# PanoBoardV4.net
KiCad netlist of a schematic drawn in EAGLE
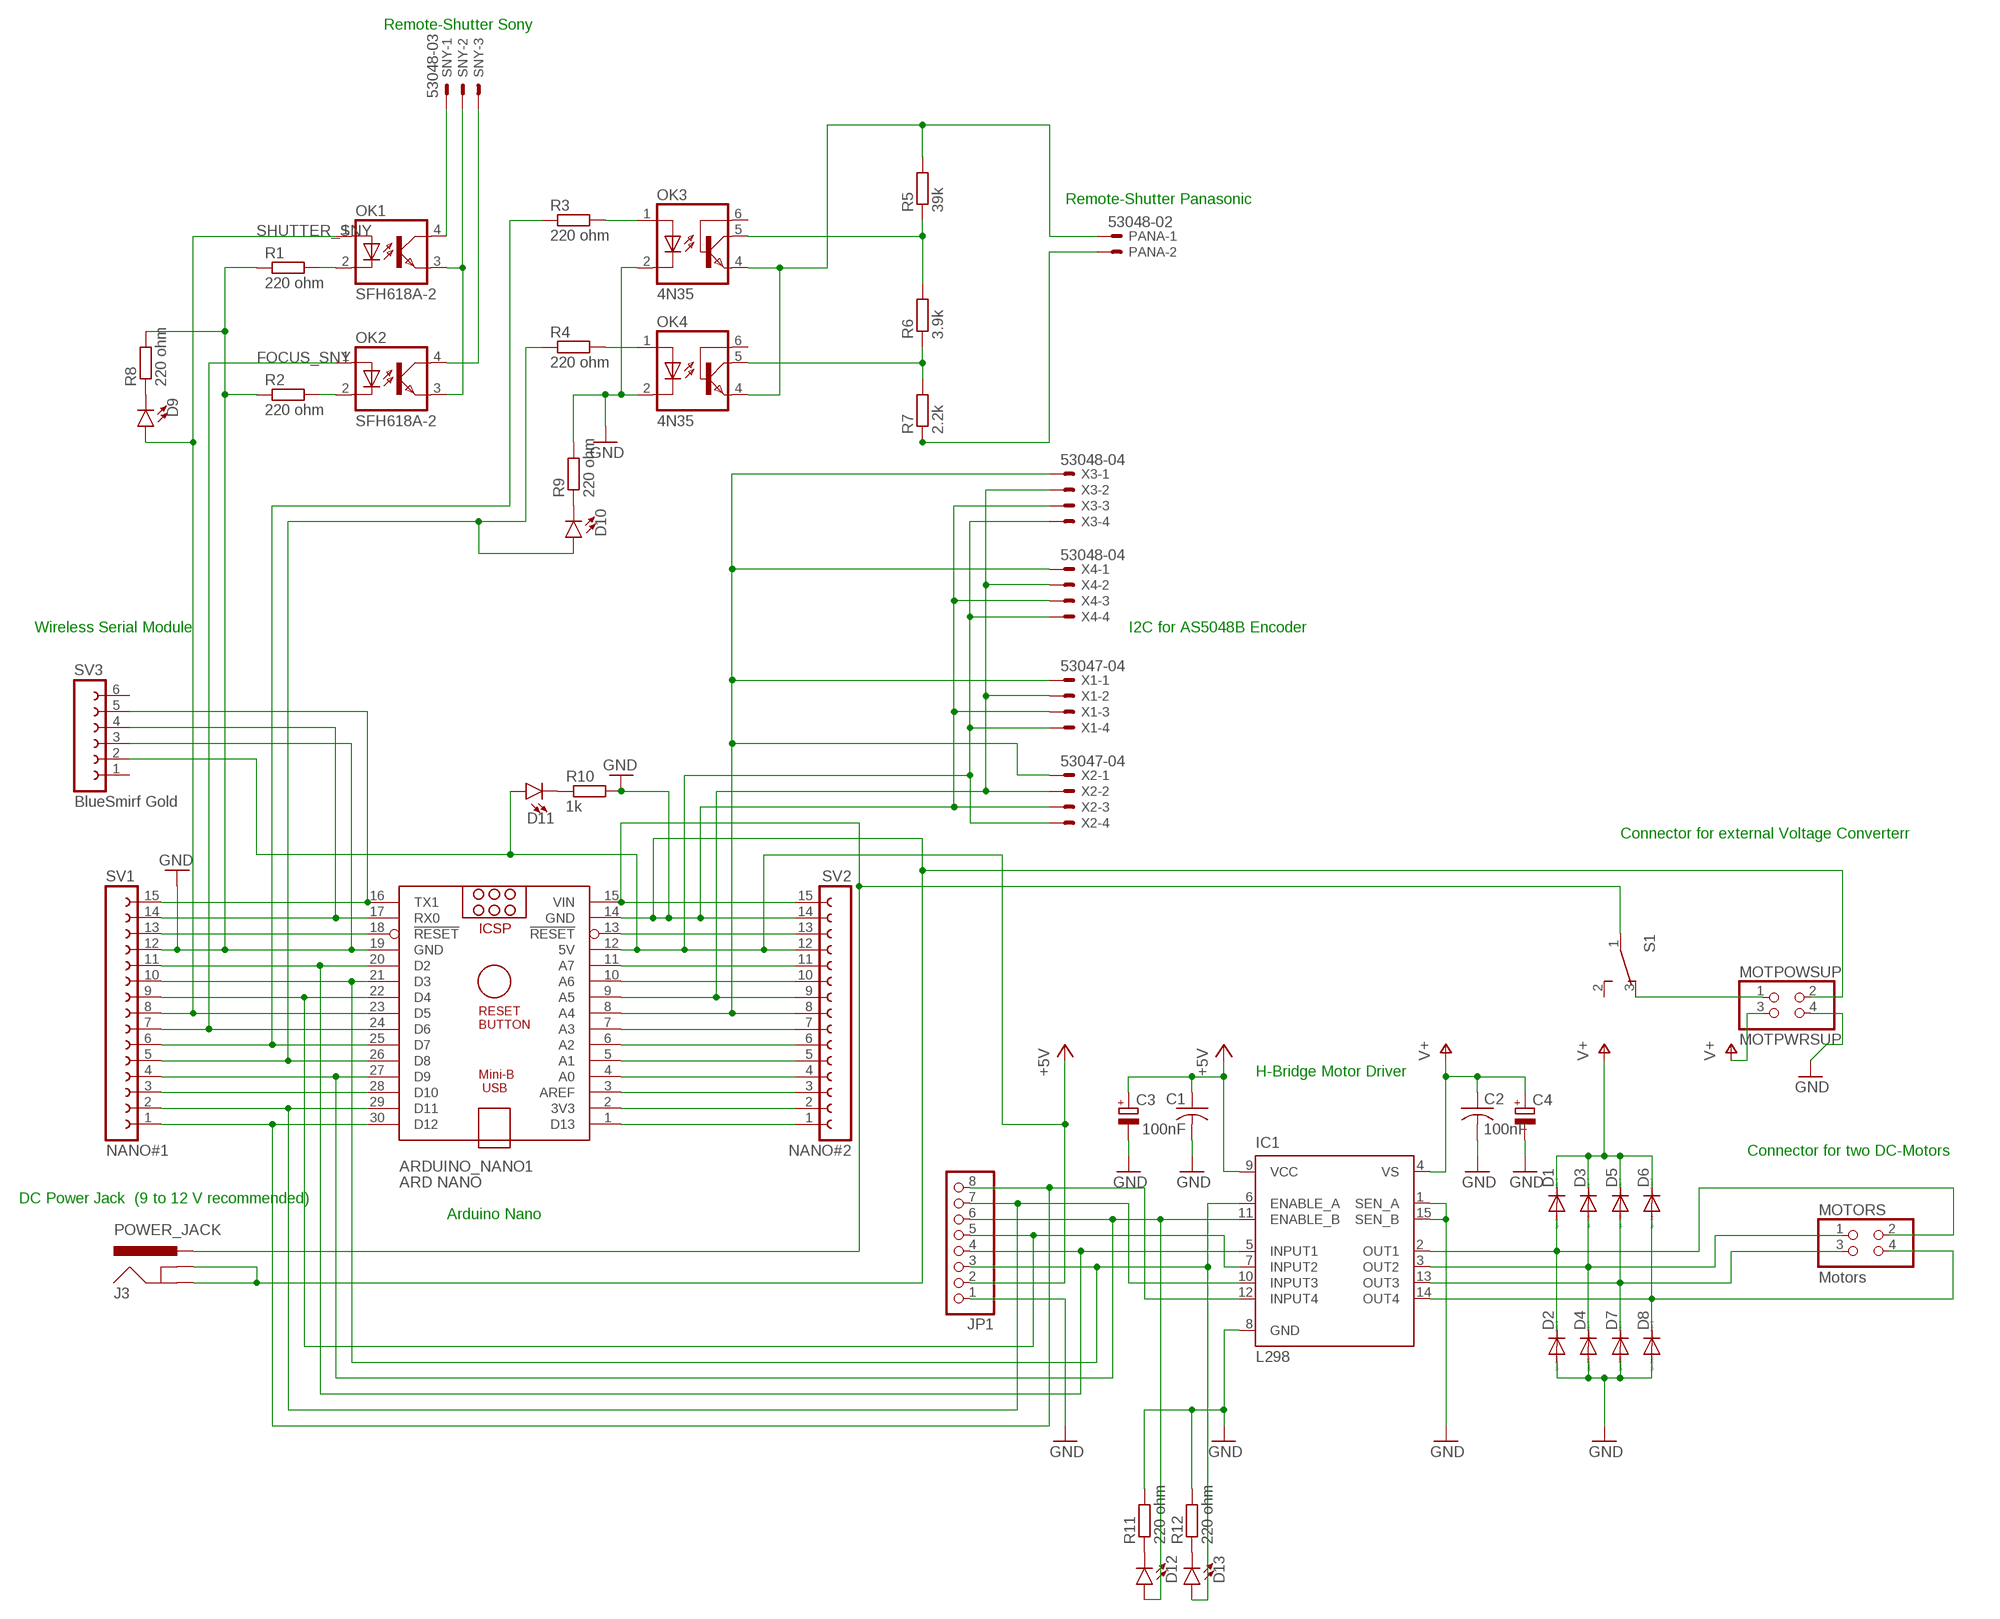
[diagram p0: schematic, sheet 1]

(export (version "E")
  (design (tool "Eeschema 10.0.6"))
  (components
    (comp (ref "ARDUINO_NANO1")
      (value "ARD NANO")
      (footprint "eagle-import:ARDUINO_NANO")
      (libsource (lib "eagle-import") (part "ARDUINO_NANO"))
    )
    (comp (ref "C1")
      (value "100nF")
      (footprint "eagle-import:C050-024X044")
      (libsource (lib "eagle-import") (part "C-US050-024X044"))
    )
    (comp (ref "C2")
      (value "100nF")
      (footprint "eagle-import:C050-024X044")
      (libsource (lib "eagle-import") (part "C-US050-024X044"))
    )
    (comp (ref "C3")
      (value "CPOL-EUE3.5-10")
      (footprint "eagle-import:E3,5-10")
      (libsource (lib "eagle-import") (part "CPOL-EUE3.5-10"))
    )
    (comp (ref "C4")
      (value "CPOL-EUE3.5-10")
      (footprint "eagle-import:E3,5-10")
      (libsource (lib "eagle-import") (part "CPOL-EUE3.5-10"))
    )
    (comp (ref "D1")
      (value "DIODE-D-5")
      (footprint "eagle-import:D-5")
      (libsource (lib "eagle-import") (part "DIODE-D-5"))
    )
    (comp (ref "D2")
      (value "DIODE-D-5")
      (footprint "eagle-import:D-5")
      (libsource (lib "eagle-import") (part "DIODE-D-5"))
    )
    (comp (ref "D3")
      (value "DIODE-D-5")
      (footprint "eagle-import:D-5")
      (libsource (lib "eagle-import") (part "DIODE-D-5"))
    )
    (comp (ref "D4")
      (value "DIODE-D-5")
      (footprint "eagle-import:D-5")
      (libsource (lib "eagle-import") (part "DIODE-D-5"))
    )
    (comp (ref "D5")
      (value "DIODE-D-5")
      (footprint "eagle-import:D-5")
      (libsource (lib "eagle-import") (part "DIODE-D-5"))
    )
    (comp (ref "D6")
      (value "DIODE-D-5")
      (footprint "eagle-import:D-5")
      (libsource (lib "eagle-import") (part "DIODE-D-5"))
    )
    (comp (ref "D7")
      (value "DIODE-D-5")
      (footprint "eagle-import:D-5")
      (libsource (lib "eagle-import") (part "DIODE-D-5"))
    )
    (comp (ref "D8")
      (value "DIODE-D-5")
      (footprint "eagle-import:D-5")
      (libsource (lib "eagle-import") (part "DIODE-D-5"))
    )
    (comp (ref "D9")
      (value "LED1206")
      (footprint "eagle-import:LED-1206")
      (libsource (lib "eagle-import") (part "LED1206"))
    )
    (comp (ref "D10")
      (value "LED1206")
      (footprint "eagle-import:LED-1206")
      (libsource (lib "eagle-import") (part "LED1206"))
    )
    (comp (ref "D11")
      (value "LED1206")
      (footprint "eagle-import:LED-1206")
      (libsource (lib "eagle-import") (part "LED1206"))
    )
    (comp (ref "D12")
      (value "LED1206")
      (footprint "eagle-import:LED-1206")
      (libsource (lib "eagle-import") (part "LED1206"))
    )
    (comp (ref "D13")
      (value "LED1206")
      (footprint "eagle-import:LED-1206")
      (libsource (lib "eagle-import") (part "LED1206"))
    )
    (comp (ref "IC1")
      (value "L298")
      (footprint "eagle-import:MULTIWATT-15")
      (libsource (lib "eagle-import") (part "L298"))
    )
    (comp (ref "J3")
      (value "POWER_JACK")
      (footprint "eagle-import:POWER_JACK_PTH")
      (libsource (lib "eagle-import") (part "POWER_JACK"))
    )
    (comp (ref "JP1")
      (value "PINHD-1X8")
      (footprint "eagle-import:1X08")
      (libsource (lib "eagle-import") (part "PINHD-1X8"))
    )
    (comp (ref "MOTORS")
      (value "Motors")
      (footprint "eagle-import:2X02")
      (libsource (lib "eagle-import") (part "PINHD-2X2"))
    )
    (comp (ref "MOTPOWSUP")
      (value "MOTPWRSUP")
      (footprint "eagle-import:2X02")
      (libsource (lib "eagle-import") (part "PINHD-2X2"))
    )
    (comp (ref "OK1")
      (value "SFH618A-2")
      (footprint "eagle-import:DIP4")
      (fields (field (name "MF") "VISHAY/TELEFUNKEN"))
      (libsource (lib "eagle-import") (part "SFH618?A-2"))
    )
    (comp (ref "OK2")
      (value "SFH618A-2")
      (footprint "eagle-import:DIP4")
      (fields (field (name "MF") "VISHAY/TELEFUNKEN"))
      (libsource (lib "eagle-import") (part "SFH618?A-2"))
    )
    (comp (ref "OK3")
      (value "4N35")
      (footprint "eagle-import:DIL06")
      (fields (field (name "MF") "FAIRCHILD SEMICONDUCTOR"))
      (libsource (lib "eagle-import") (part "4N35"))
    )
    (comp (ref "OK4")
      (value "4N35")
      (footprint "eagle-import:DIL06")
      (fields (field (name "MF") "FAIRCHILD SEMICONDUCTOR"))
      (libsource (lib "eagle-import") (part "4N35"))
    )
    (comp (ref "PANA")
      (value "53048-02")
      (footprint "eagle-import:53048-02")
      (fields (field (name "MF") "MOLEX") (field (name "MPN") "53048-0210"))
      (libsource (lib "eagle-import") (part "53?-02048"))
    )
    (comp (ref "R1")
      (value "220 ohm")
      (footprint "eagle-import:R1210")
      (libsource (lib "eagle-import") (part "R-EU_R1210"))
    )
    (comp (ref "R2")
      (value "220 ohm")
      (footprint "eagle-import:R1210")
      (libsource (lib "eagle-import") (part "R-EU_R1210"))
    )
    (comp (ref "R3")
      (value "220 ohm")
      (footprint "eagle-import:R1210")
      (libsource (lib "eagle-import") (part "R-EU_R1210"))
    )
    (comp (ref "R4")
      (value "220 ohm")
      (footprint "eagle-import:R1210")
      (libsource (lib "eagle-import") (part "R-EU_R1210"))
    )
    (comp (ref "R5")
      (value "39k")
      (footprint "eagle-import:R1210")
      (libsource (lib "eagle-import") (part "R-EU_R1210"))
    )
    (comp (ref "R6")
      (value "3.9k")
      (footprint "eagle-import:R1210")
      (libsource (lib "eagle-import") (part "R-EU_R1210"))
    )
    (comp (ref "R7")
      (value "2.2k")
      (footprint "eagle-import:R1210")
      (libsource (lib "eagle-import") (part "R-EU_R1210"))
    )
    (comp (ref "R8")
      (value "220 ohm")
      (footprint "eagle-import:R1210")
      (libsource (lib "eagle-import") (part "R-EU_R1210"))
    )
    (comp (ref "R9")
      (value "220 ohm")
      (footprint "eagle-import:R1210")
      (libsource (lib "eagle-import") (part "R-EU_R1210"))
    )
    (comp (ref "R10")
      (value "1k")
      (footprint "eagle-import:R1210")
      (libsource (lib "eagle-import") (part "R-EU_R1210"))
    )
    (comp (ref "R11")
      (value "220 ohm")
      (footprint "eagle-import:R1210")
      (libsource (lib "eagle-import") (part "R-EU_R1210"))
    )
    (comp (ref "R12")
      (value "220 ohm")
      (footprint "eagle-import:R1210")
      (libsource (lib "eagle-import") (part "R-EU_R1210"))
    )
    (comp (ref "S1")
      (value "450302014072")
      (footprint "eagle-import:450302014072")
      (libsource (lib "eagle-import") (part "450302014072"))
    )
    (comp (ref "SNY")
      (value "53048-03")
      (footprint "eagle-import:53048-03")
      (fields (field (name "MF") "WALDOM/MOLEX") (field (name "MPN") "53048-0310"))
      (libsource (lib "eagle-import") (part "53?-03048"))
    )
    (comp (ref "SV1")
      (value "NANO#1")
      (footprint "eagle-import:FE15")
      (libsource (lib "eagle-import") (part "FE15-1"))
    )
    (comp (ref "SV2")
      (value "NANO#2")
      (footprint "eagle-import:FE15")
      (libsource (lib "eagle-import") (part "FE15-1"))
    )
    (comp (ref "SV3")
      (value "BlueSmirf Gold")
      (footprint "eagle-import:FE06W")
      (libsource (lib "eagle-import") (part "FE06W"))
    )
    (comp (ref "X1")
      (value "53047-04")
      (footprint "eagle-import:53047-04")
      (fields (field (name "MF") "WALDOM/MOLEX") (field (name "MPN") "53047-0410"))
      (libsource (lib "eagle-import") (part "53?-04047"))
    )
    (comp (ref "X2")
      (value "53047-04")
      (footprint "eagle-import:53047-04")
      (fields (field (name "MF") "WALDOM/MOLEX") (field (name "MPN") "53047-0410"))
      (libsource (lib "eagle-import") (part "53?-04047"))
    )
    (comp (ref "X3")
      (value "53048-04")
      (footprint "eagle-import:53048-04")
      (fields (field (name "MF") "MOLEX") (field (name "MPN") "53048-0410"))
      (libsource (lib "eagle-import") (part "53?-04048"))
    )
    (comp (ref "X4")
      (value "53048-04")
      (footprint "eagle-import:53048-04")
      (fields (field (name "MF") "MOLEX") (field (name "MPN") "53048-0410"))
      (libsource (lib "eagle-import") (part "53?-04048"))
    )
  )
  (nets
    (net (code "1") (name "+5V") (class "Default")
      (node (ref "ARDUINO_NANO1") (pin "12") (pinfunction "5V_12") (pintype "power_in"))
      (node (ref "C1") (pin "1") (pinfunction "1_1") (pintype "passive"))
      (node (ref "C3") (pin "+") (pinfunction "+_+") (pintype "passive"))
      (node (ref "D11") (pin "A") (pinfunction "A_A") (pintype "passive"))
      (node (ref "IC1") (pin "9") (pinfunction "VCC_9") (pintype "power_in"))
      (node (ref "JP1") (pin "2") (pinfunction "2_2") (pintype "passive"))
      (node (ref "SV2") (pin "12") (pinfunction "12_12") (pintype "passive"))
      (node (ref "SV3") (pin "2") (pinfunction "2_2") (pintype "passive"))
      (node (ref "X1") (pin "4") (pinfunction "S_4") (pintype "passive"))
      (node (ref "X2") (pin "4") (pinfunction "S_4") (pintype "passive"))
      (node (ref "X3") (pin "4") (pinfunction "S_4") (pintype "passive"))
      (node (ref "X4") (pin "4") (pinfunction "S_4") (pintype "passive"))
    )
    (net (code "2") (name "/FOCUS_SNY") (class "Default")
      (node (ref "ARDUINO_NANO1") (pin "24") (pinfunction "D6_24") (pintype "bidirectional"))
      (node (ref "OK2") (pin "1") (pinfunction "A_1") (pintype "passive"))
      (node (ref "SV1") (pin "7") (pinfunction "7_7") (pintype "passive"))
    )
    (net (code "3") (name "/SHUTTER_SNY") (class "Default")
      (node (ref "ARDUINO_NANO1") (pin "23") (pinfunction "D5_23") (pintype "bidirectional"))
      (node (ref "D9") (pin "A") (pinfunction "A_A") (pintype "passive"))
      (node (ref "OK1") (pin "1") (pinfunction "A_1") (pintype "passive"))
      (node (ref "SV1") (pin "8") (pinfunction "8_8") (pintype "passive"))
    )
    (net (code "4") (name "GND") (class "Default")
      (node (ref "ARDUINO_NANO1") (pin "14") (pinfunction "GND_14") (pintype "power_in"))
      (node (ref "ARDUINO_NANO1") (pin "19") (pinfunction "GND_19") (pintype "power_in"))
      (node (ref "C1") (pin "2") (pinfunction "2_2") (pintype "passive"))
      (node (ref "C2") (pin "2") (pinfunction "2_2") (pintype "passive"))
      (node (ref "C3") (pin "-") (pinfunction "-_-") (pintype "passive"))
      (node (ref "C4") (pin "-") (pinfunction "-_-") (pintype "passive"))
      (node (ref "D2") (pin "A") (pinfunction "A_A") (pintype "passive"))
      (node (ref "D4") (pin "A") (pinfunction "A_A") (pintype "passive"))
      (node (ref "D7") (pin "A") (pinfunction "A_A") (pintype "passive"))
      (node (ref "D8") (pin "A") (pinfunction "A_A") (pintype "passive"))
      (node (ref "IC1") (pin "1") (pinfunction "SEN_A_1") (pintype "input"))
      (node (ref "IC1") (pin "15") (pinfunction "SEN_B_15") (pintype "input"))
      (node (ref "IC1") (pin "8") (pinfunction "GND_8") (pintype "power_in"))
      (node (ref "J3") (pin "GND") (pinfunction "GND_GND") (pintype "bidirectional"))
      (node (ref "J3") (pin "GNDBREAK") (pinfunction "GNDBREAK_GNDBREAK") (pintype "bidirectional"))
      (node (ref "JP1") (pin "1") (pinfunction "1_1") (pintype "passive"))
      (node (ref "MOTPOWSUP") (pin "2") (pinfunction "2_2") (pintype "passive"))
      (node (ref "MOTPOWSUP") (pin "4") (pinfunction "4_4") (pintype "passive"))
      (node (ref "OK3") (pin "2") (pinfunction "C_2") (pintype "passive"))
      (node (ref "OK4") (pin "2") (pinfunction "C_2") (pintype "passive"))
      (node (ref "R1") (pin "1") (pinfunction "1_1") (pintype "passive"))
      (node (ref "R10") (pin "2") (pinfunction "2_2") (pintype "passive"))
      (node (ref "R11") (pin "2") (pinfunction "2_2") (pintype "passive"))
      (node (ref "R12") (pin "2") (pinfunction "2_2") (pintype "passive"))
      (node (ref "R2") (pin "1") (pinfunction "1_1") (pintype "passive"))
      (node (ref "R8") (pin "2") (pinfunction "2_2") (pintype "passive"))
      (node (ref "R9") (pin "2") (pinfunction "2_2") (pintype "passive"))
      (node (ref "SV1") (pin "12") (pinfunction "12_12") (pintype "passive"))
      (node (ref "SV2") (pin "14") (pinfunction "14_14") (pintype "passive"))
      (node (ref "SV3") (pin "3") (pinfunction "3_3") (pintype "passive"))
      (node (ref "X1") (pin "3") (pinfunction "S_3") (pintype "passive"))
      (node (ref "X2") (pin "3") (pinfunction "S_3") (pintype "passive"))
      (node (ref "X3") (pin "3") (pinfunction "S_3") (pintype "passive"))
      (node (ref "X4") (pin "3") (pinfunction "S_3") (pintype "passive"))
    )
    (net (code "5") (name "Net-(ARDUINO_NANO1-3V3)") (class "Default")
      (node (ref "ARDUINO_NANO1") (pin "2") (pinfunction "3V3_2") (pintype "output"))
      (node (ref "SV2") (pin "2") (pinfunction "2_2") (pintype "passive"))
    )
    (net (code "6") (name "Net-(ARDUINO_NANO1-A0)") (class "Default")
      (node (ref "ARDUINO_NANO1") (pin "4") (pinfunction "A0_4") (pintype "bidirectional"))
      (node (ref "SV2") (pin "4") (pinfunction "4_4") (pintype "passive"))
    )
    (net (code "7") (name "Net-(ARDUINO_NANO1-A1)") (class "Default")
      (node (ref "ARDUINO_NANO1") (pin "5") (pinfunction "A1_5") (pintype "bidirectional"))
      (node (ref "SV2") (pin "5") (pinfunction "5_5") (pintype "passive"))
    )
    (net (code "8") (name "Net-(ARDUINO_NANO1-A2)") (class "Default")
      (node (ref "ARDUINO_NANO1") (pin "6") (pinfunction "A2_6") (pintype "bidirectional"))
      (node (ref "SV2") (pin "6") (pinfunction "6_6") (pintype "passive"))
    )
    (net (code "9") (name "Net-(ARDUINO_NANO1-A3)") (class "Default")
      (node (ref "ARDUINO_NANO1") (pin "7") (pinfunction "A3_7") (pintype "bidirectional"))
      (node (ref "SV2") (pin "7") (pinfunction "7_7") (pintype "passive"))
    )
    (net (code "10") (name "Net-(ARDUINO_NANO1-A4)") (class "Default")
      (node (ref "ARDUINO_NANO1") (pin "8") (pinfunction "A4_8") (pintype "bidirectional"))
      (node (ref "SV2") (pin "8") (pinfunction "8_8") (pintype "passive"))
      (node (ref "X1") (pin "1") (pinfunction "S_1") (pintype "passive"))
      (node (ref "X2") (pin "1") (pinfunction "S_1") (pintype "passive"))
      (node (ref "X3") (pin "1") (pinfunction "S_1") (pintype "passive"))
      (node (ref "X4") (pin "1") (pinfunction "S_1") (pintype "passive"))
    )
    (net (code "11") (name "Net-(ARDUINO_NANO1-A5)") (class "Default")
      (node (ref "ARDUINO_NANO1") (pin "9") (pinfunction "A5_9") (pintype "bidirectional"))
      (node (ref "SV2") (pin "9") (pinfunction "9_9") (pintype "passive"))
      (node (ref "X1") (pin "2") (pinfunction "S_2") (pintype "passive"))
      (node (ref "X2") (pin "2") (pinfunction "S_2") (pintype "passive"))
      (node (ref "X3") (pin "2") (pinfunction "S_2") (pintype "passive"))
      (node (ref "X4") (pin "2") (pinfunction "S_2") (pintype "passive"))
    )
    (net (code "12") (name "Net-(ARDUINO_NANO1-A6)") (class "Default")
      (node (ref "ARDUINO_NANO1") (pin "10") (pinfunction "A6_10") (pintype "bidirectional"))
      (node (ref "SV2") (pin "10") (pinfunction "10_10") (pintype "passive"))
    )
    (net (code "13") (name "Net-(ARDUINO_NANO1-A7)") (class "Default")
      (node (ref "ARDUINO_NANO1") (pin "11") (pinfunction "A7_11") (pintype "bidirectional"))
      (node (ref "SV2") (pin "11") (pinfunction "11_11") (pintype "passive"))
    )
    (net (code "14") (name "Net-(ARDUINO_NANO1-AREF)") (class "Default")
      (node (ref "ARDUINO_NANO1") (pin "3") (pinfunction "AREF_3") (pintype "input"))
      (node (ref "SV2") (pin "3") (pinfunction "3_3") (pintype "passive"))
    )
    (net (code "15") (name "Net-(ARDUINO_NANO1-D2)") (class "Default")
      (node (ref "ARDUINO_NANO1") (pin "20") (pinfunction "D2_20") (pintype "bidirectional"))
      (node (ref "IC1") (pin "5") (pinfunction "INPUT1_5") (pintype "input"))
      (node (ref "JP1") (pin "4") (pinfunction "4_4") (pintype "passive"))
      (node (ref "SV1") (pin "11") (pinfunction "11_11") (pintype "passive"))
    )
    (net (code "16") (name "Net-(ARDUINO_NANO1-D3)") (class "Default")
      (node (ref "ARDUINO_NANO1") (pin "21") (pinfunction "D3_21") (pintype "bidirectional"))
      (node (ref "D13") (pin "A") (pinfunction "A_A") (pintype "passive"))
      (node (ref "IC1") (pin "6") (pinfunction "ENABLE_A_6") (pintype "input"))
      (node (ref "JP1") (pin "3") (pinfunction "3_3") (pintype "passive"))
      (node (ref "SV1") (pin "10") (pinfunction "10_10") (pintype "passive"))
    )
    (net (code "17") (name "Net-(ARDUINO_NANO1-D4)") (class "Default")
      (node (ref "ARDUINO_NANO1") (pin "22") (pinfunction "D4_22") (pintype "bidirectional"))
      (node (ref "IC1") (pin "7") (pinfunction "INPUT2_7") (pintype "input"))
      (node (ref "JP1") (pin "5") (pinfunction "5_5") (pintype "passive"))
      (node (ref "SV1") (pin "9") (pinfunction "9_9") (pintype "passive"))
    )
    (net (code "18") (name "Net-(ARDUINO_NANO1-D7)") (class "Default")
      (node (ref "ARDUINO_NANO1") (pin "25") (pinfunction "D7_25") (pintype "bidirectional"))
      (node (ref "R3") (pin "1") (pinfunction "1_1") (pintype "passive"))
      (node (ref "SV1") (pin "6") (pinfunction "6_6") (pintype "passive"))
    )
    (net (code "19") (name "Net-(ARDUINO_NANO1-D8)") (class "Default")
      (node (ref "ARDUINO_NANO1") (pin "26") (pinfunction "D8_26") (pintype "bidirectional"))
      (node (ref "D10") (pin "A") (pinfunction "A_A") (pintype "passive"))
      (node (ref "R4") (pin "1") (pinfunction "1_1") (pintype "passive"))
      (node (ref "SV1") (pin "5") (pinfunction "5_5") (pintype "passive"))
    )
    (net (code "20") (name "Net-(ARDUINO_NANO1-D9)") (class "Default")
      (node (ref "ARDUINO_NANO1") (pin "27") (pinfunction "D9_27") (pintype "bidirectional"))
      (node (ref "D12") (pin "A") (pinfunction "A_A") (pintype "passive"))
      (node (ref "IC1") (pin "11") (pinfunction "ENABLE_B_11") (pintype "input"))
      (node (ref "JP1") (pin "6") (pinfunction "6_6") (pintype "passive"))
      (node (ref "SV1") (pin "4") (pinfunction "4_4") (pintype "passive"))
    )
    (net (code "21") (name "Net-(ARDUINO_NANO1-D10)") (class "Default")
      (node (ref "ARDUINO_NANO1") (pin "28") (pinfunction "D10_28") (pintype "bidirectional"))
      (node (ref "SV1") (pin "3") (pinfunction "3_3") (pintype "passive"))
    )
    (net (code "22") (name "Net-(ARDUINO_NANO1-D11)") (class "Default")
      (node (ref "ARDUINO_NANO1") (pin "29") (pinfunction "D11_29") (pintype "bidirectional"))
      (node (ref "IC1") (pin "10") (pinfunction "INPUT3_10") (pintype "input"))
      (node (ref "JP1") (pin "7") (pinfunction "7_7") (pintype "passive"))
      (node (ref "SV1") (pin "2") (pinfunction "2_2") (pintype "passive"))
    )
    (net (code "23") (name "Net-(ARDUINO_NANO1-D12)") (class "Default")
      (node (ref "ARDUINO_NANO1") (pin "30") (pinfunction "D12_30") (pintype "bidirectional"))
      (node (ref "IC1") (pin "12") (pinfunction "INPUT4_12") (pintype "input"))
      (node (ref "JP1") (pin "8") (pinfunction "8_8") (pintype "passive"))
      (node (ref "SV1") (pin "1") (pinfunction "1_1") (pintype "passive"))
    )
    (net (code "24") (name "Net-(ARDUINO_NANO1-D13)") (class "Default")
      (node (ref "ARDUINO_NANO1") (pin "1") (pinfunction "D13_1") (pintype "bidirectional"))
      (node (ref "SV2") (pin "1") (pinfunction "1_1") (pintype "passive"))
    )
    (net (code "25") (name "Net-(ARDUINO_NANO1-RX0)") (class "Default")
      (node (ref "ARDUINO_NANO1") (pin "17") (pinfunction "RX0_17") (pintype "bidirectional"))
      (node (ref "SV1") (pin "14") (pinfunction "14_14") (pintype "passive"))
      (node (ref "SV3") (pin "4") (pinfunction "4_4") (pintype "passive"))
    )
    (net (code "26") (name "Net-(ARDUINO_NANO1-TX1)") (class "Default")
      (node (ref "ARDUINO_NANO1") (pin "16") (pinfunction "TX1_16") (pintype "bidirectional"))
      (node (ref "SV1") (pin "15") (pinfunction "15_15") (pintype "passive"))
      (node (ref "SV3") (pin "5") (pinfunction "5_5") (pintype "passive"))
    )
    (net (code "27") (name "Net-(ARDUINO_NANO1-VIN)") (class "Default")
      (node (ref "ARDUINO_NANO1") (pin "15") (pinfunction "VIN_15") (pintype "power_in"))
      (node (ref "J3") (pin "PWR") (pinfunction "PWR_PWR") (pintype "bidirectional"))
      (node (ref "S1") (pin "1") (pinfunction "1_1") (pintype "passive"))
      (node (ref "SV2") (pin "15") (pinfunction "15_15") (pintype "passive"))
    )
    (net (code "28") (name "Net-(ARDUINO_NANO1-~{RESET}-Pad13)") (class "Default")
      (node (ref "ARDUINO_NANO1") (pin "13") (pinfunction "~{RESET}_13") (pintype "input"))
      (node (ref "SV2") (pin "13") (pinfunction "13_13") (pintype "passive"))
    )
    (net (code "29") (name "Net-(ARDUINO_NANO1-~{RESET}-Pad18)") (class "Default")
      (node (ref "ARDUINO_NANO1") (pin "18") (pinfunction "~{RESET}_18") (pintype "input"))
      (node (ref "SV1") (pin "13") (pinfunction "13_13") (pintype "passive"))
    )
    (net (code "30") (name "Net-(D9-PadC)") (class "Default")
      (node (ref "D9") (pin "C") (pinfunction "C_C") (pintype "passive"))
      (node (ref "R8") (pin "1") (pinfunction "1_1") (pintype "passive"))
    )
    (net (code "31") (name "Net-(D10-PadC)") (class "Default")
      (node (ref "D10") (pin "C") (pinfunction "C_C") (pintype "passive"))
      (node (ref "R9") (pin "1") (pinfunction "1_1") (pintype "passive"))
    )
    (net (code "32") (name "Net-(D11-PadC)") (class "Default")
      (node (ref "D11") (pin "C") (pinfunction "C_C") (pintype "passive"))
      (node (ref "R10") (pin "1") (pinfunction "1_1") (pintype "passive"))
    )
    (net (code "33") (name "Net-(D12-PadC)") (class "Default")
      (node (ref "D12") (pin "C") (pinfunction "C_C") (pintype "passive"))
      (node (ref "R11") (pin "1") (pinfunction "1_1") (pintype "passive"))
    )
    (net (code "34") (name "Net-(D13-PadC)") (class "Default")
      (node (ref "D13") (pin "C") (pinfunction "C_C") (pintype "passive"))
      (node (ref "R12") (pin "1") (pinfunction "1_1") (pintype "passive"))
    )
    (net (code "35") (name "Net-(IC1-OUT1)") (class "Default")
      (node (ref "D1") (pin "A") (pinfunction "A_A") (pintype "passive"))
      (node (ref "D2") (pin "C") (pinfunction "C_C") (pintype "passive"))
      (node (ref "IC1") (pin "2") (pinfunction "OUT1_2") (pintype "output"))
      (node (ref "MOTORS") (pin "2") (pinfunction "2_2") (pintype "passive"))
    )
    (net (code "36") (name "Net-(IC1-OUT2)") (class "Default")
      (node (ref "D3") (pin "A") (pinfunction "A_A") (pintype "passive"))
      (node (ref "D4") (pin "C") (pinfunction "C_C") (pintype "passive"))
      (node (ref "IC1") (pin "3") (pinfunction "OUT2_3") (pintype "output"))
      (node (ref "MOTORS") (pin "1") (pinfunction "1_1") (pintype "passive"))
    )
    (net (code "37") (name "Net-(IC1-OUT3)") (class "Default")
      (node (ref "D5") (pin "A") (pinfunction "A_A") (pintype "passive"))
      (node (ref "D7") (pin "C") (pinfunction "C_C") (pintype "passive"))
      (node (ref "IC1") (pin "13") (pinfunction "OUT3_13") (pintype "output"))
      (node (ref "MOTORS") (pin "3") (pinfunction "3_3") (pintype "passive"))
    )
    (net (code "38") (name "Net-(IC1-OUT4)") (class "Default")
      (node (ref "D6") (pin "A") (pinfunction "A_A") (pintype "passive"))
      (node (ref "D8") (pin "C") (pinfunction "C_C") (pintype "passive"))
      (node (ref "IC1") (pin "14") (pinfunction "OUT4_14") (pintype "output"))
      (node (ref "MOTORS") (pin "4") (pinfunction "4_4") (pintype "passive"))
    )
    (net (code "39") (name "Net-(MOTPOWSUP-Pad1)") (class "Default")
      (node (ref "MOTPOWSUP") (pin "1") (pinfunction "1_1") (pintype "passive"))
      (node (ref "S1") (pin "3") (pinfunction "3_3") (pintype "passive"))
    )
    (net (code "40") (name "Net-(OK1-C)") (class "Default")
      (node (ref "OK1") (pin "2") (pinfunction "C_2") (pintype "passive"))
      (node (ref "R1") (pin "2") (pinfunction "2_2") (pintype "passive"))
    )
    (net (code "41") (name "Net-(OK1-COL)") (class "Default")
      (node (ref "OK1") (pin "4") (pinfunction "COL_4") (pintype "passive"))
      (node (ref "SNY") (pin "1") (pinfunction "S_1") (pintype "passive"))
    )
    (net (code "42") (name "Net-(OK1-EMIT)") (class "Default")
      (node (ref "OK1") (pin "3") (pinfunction "EMIT_3") (pintype "passive"))
      (node (ref "OK2") (pin "3") (pinfunction "EMIT_3") (pintype "passive"))
      (node (ref "SNY") (pin "2") (pinfunction "S_2") (pintype "passive"))
    )
    (net (code "43") (name "Net-(OK2-C)") (class "Default")
      (node (ref "OK2") (pin "2") (pinfunction "C_2") (pintype "passive"))
      (node (ref "R2") (pin "2") (pinfunction "2_2") (pintype "passive"))
    )
    (net (code "44") (name "Net-(OK2-COL)") (class "Default")
      (node (ref "OK2") (pin "4") (pinfunction "COL_4") (pintype "passive"))
      (node (ref "SNY") (pin "3") (pinfunction "S_3") (pintype "passive"))
    )
    (net (code "45") (name "Net-(OK3-A)") (class "Default")
      (node (ref "OK3") (pin "1") (pinfunction "A_1") (pintype "passive"))
      (node (ref "R3") (pin "2") (pinfunction "2_2") (pintype "passive"))
    )
    (net (code "46") (name "Net-(OK3-COL)") (class "Default")
      (node (ref "OK3") (pin "5") (pinfunction "COL_5") (pintype "passive"))
      (node (ref "R5") (pin "1") (pinfunction "1_1") (pintype "passive"))
      (node (ref "R6") (pin "2") (pinfunction "2_2") (pintype "passive"))
    )
    (net (code "47") (name "Net-(OK3-EMI)") (class "Default")
      (node (ref "OK3") (pin "4") (pinfunction "EMI_4") (pintype "passive"))
      (node (ref "OK4") (pin "4") (pinfunction "EMI_4") (pintype "passive"))
      (node (ref "PANA") (pin "1") (pinfunction "S_1") (pintype "passive"))
      (node (ref "R5") (pin "2") (pinfunction "2_2") (pintype "passive"))
    )
    (net (code "48") (name "Net-(OK4-A)") (class "Default")
      (node (ref "OK4") (pin "1") (pinfunction "A_1") (pintype "passive"))
      (node (ref "R4") (pin "2") (pinfunction "2_2") (pintype "passive"))
    )
    (net (code "49") (name "Net-(OK4-COL)") (class "Default")
      (node (ref "OK4") (pin "5") (pinfunction "COL_5") (pintype "passive"))
      (node (ref "R6") (pin "1") (pinfunction "1_1") (pintype "passive"))
      (node (ref "R7") (pin "2") (pinfunction "2_2") (pintype "passive"))
    )
    (net (code "50") (name "Net-(PANAB-S)") (class "Default")
      (node (ref "PANA") (pin "2") (pinfunction "S_2") (pintype "passive"))
      (node (ref "R7") (pin "1") (pinfunction "1_1") (pintype "passive"))
    )
    (net (code "51") (name "V+") (class "Default")
      (node (ref "C2") (pin "1") (pinfunction "1_1") (pintype "passive"))
      (node (ref "C4") (pin "+") (pinfunction "+_+") (pintype "passive"))
      (node (ref "D1") (pin "C") (pinfunction "C_C") (pintype "passive"))
      (node (ref "D3") (pin "C") (pinfunction "C_C") (pintype "passive"))
      (node (ref "D5") (pin "C") (pinfunction "C_C") (pintype "passive"))
      (node (ref "D6") (pin "C") (pinfunction "C_C") (pintype "passive"))
      (node (ref "IC1") (pin "4") (pinfunction "VS_4") (pintype "power_in"))
      (node (ref "MOTPOWSUP") (pin "3") (pinfunction "3_3") (pintype "passive"))
    )
    (net (code "52") (name "unconnected-(OK3-BAS-Pad6)") (class "Default")
      (node (ref "OK3") (pin "6") (pinfunction "BAS_6") (pintype "passive"))
    )
    (net (code "53") (name "unconnected-(OK4-BAS-Pad6)") (class "Default")
      (node (ref "OK4") (pin "6") (pinfunction "BAS_6") (pintype "passive"))
    )
    (net (code "54") (name "unconnected-(S1-Pad2)") (class "Default")
      (node (ref "S1") (pin "2") (pinfunction "2_2") (pintype "passive"))
    )
    (net (code "55") (name "unconnected-(SV3-Pad1)") (class "Default")
      (node (ref "SV3") (pin "1") (pinfunction "1_1") (pintype "passive"))
    )
    (net (code "56") (name "unconnected-(SV3-Pad6)") (class "Default")
      (node (ref "SV3") (pin "6") (pinfunction "6_6") (pintype "passive"))
    )
  )
)
